# dac8.net
KiCad netlist of a schematic drawn in EAGLE
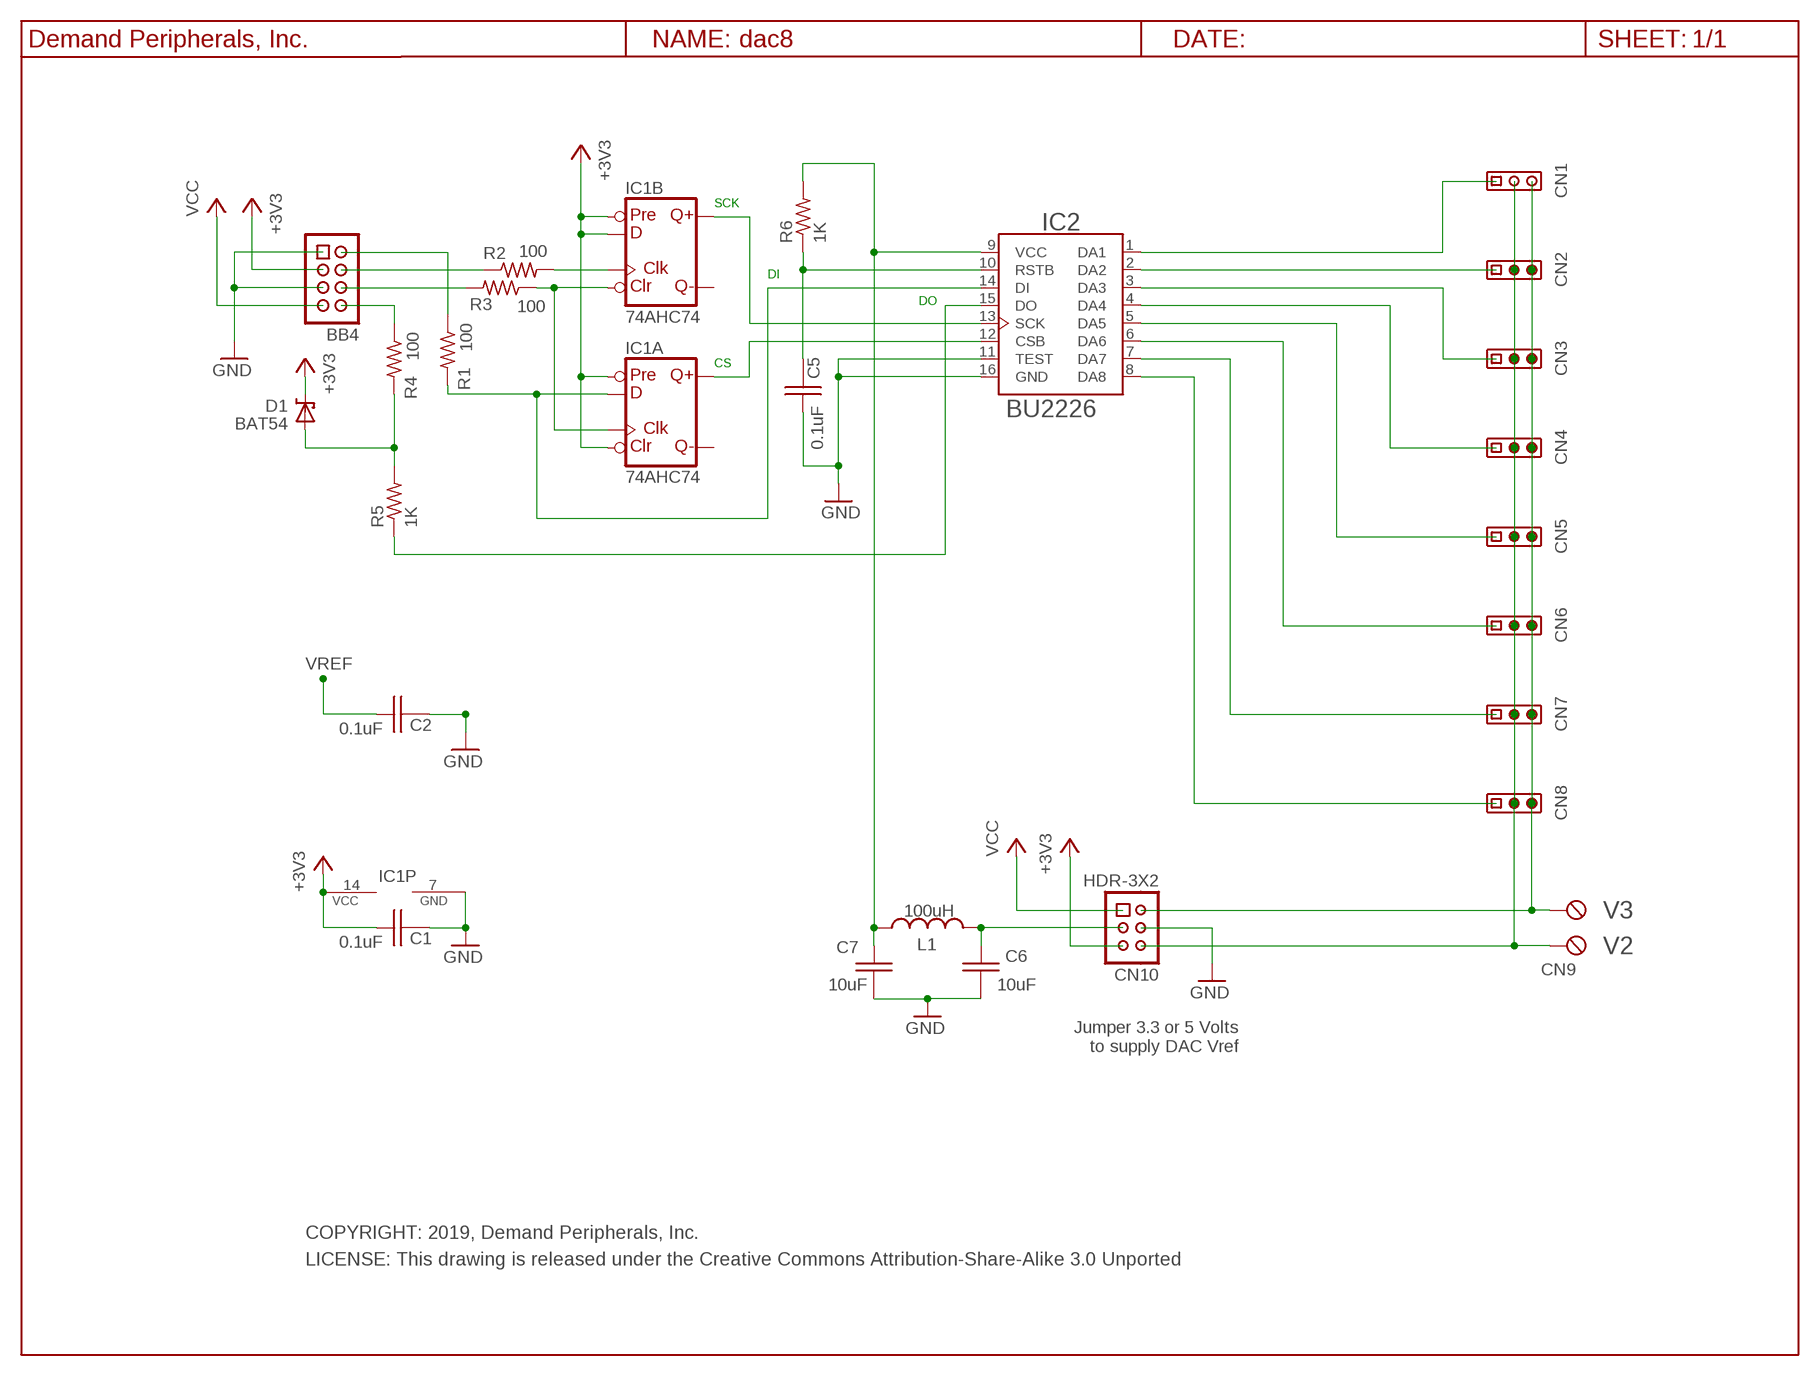
[diagram p0: schematic, sheet 1]

(export (version "E")
  (design (tool "Eeschema 10.0.6"))
  (components
    (comp (ref "BB4")
      (value "BB4")
      (footprint "eagle-import:HDR-4X2")
      (libsource (lib "eagle-import") (part "HDR-4X2-SHR"))
    )
    (comp (ref "C1")
      (value "0.1uF")
      (footprint "eagle-import:C0603")
      (libsource (lib "eagle-import") (part "C0.1UF_C0603"))
    )
    (comp (ref "C2")
      (value "0.1uF")
      (footprint "eagle-import:C0603")
      (libsource (lib "eagle-import") (part "C0.1UF_C0603"))
    )
    (comp (ref "C5")
      (value "0.1uF")
      (footprint "eagle-import:C0603")
      (libsource (lib "eagle-import") (part "C0.1UF_C0603"))
    )
    (comp (ref "C6")
      (value "10uF")
      (footprint "eagle-import:C0805")
      (libsource (lib "eagle-import") (part "C10UF35V_C0805"))
    )
    (comp (ref "C7")
      (value "10uF")
      (footprint "eagle-import:C0805")
      (libsource (lib "eagle-import") (part "C10UF35V_C0805"))
    )
    (comp (ref "CN1")
      (value "HDR-3X1")
      (footprint "eagle-import:HDR-3X1")
      (libsource (lib "eagle-import") (part "HDR-3X1"))
    )
    (comp (ref "CN2")
      (value "HDR-3X1")
      (footprint "eagle-import:HDR-3X1")
      (libsource (lib "eagle-import") (part "HDR-3X1"))
    )
    (comp (ref "CN3")
      (value "HDR-3X1")
      (footprint "eagle-import:HDR-3X1")
      (libsource (lib "eagle-import") (part "HDR-3X1"))
    )
    (comp (ref "CN4")
      (value "HDR-3X1")
      (footprint "eagle-import:HDR-3X1")
      (libsource (lib "eagle-import") (part "HDR-3X1"))
    )
    (comp (ref "CN5")
      (value "HDR-3X1")
      (footprint "eagle-import:HDR-3X1")
      (libsource (lib "eagle-import") (part "HDR-3X1"))
    )
    (comp (ref "CN6")
      (value "HDR-3X1")
      (footprint "eagle-import:HDR-3X1")
      (libsource (lib "eagle-import") (part "HDR-3X1"))
    )
    (comp (ref "CN7")
      (value "HDR-3X1")
      (footprint "eagle-import:HDR-3X1")
      (libsource (lib "eagle-import") (part "HDR-3X1"))
    )
    (comp (ref "CN8")
      (value "HDR-3X1")
      (footprint "eagle-import:HDR-3X1")
      (libsource (lib "eagle-import") (part "HDR-3X1"))
    )
    (comp (ref "CN9")
      (value "TBLK-5.08-X2")
      (footprint "eagle-import:TBLK-5.08-X2")
      (libsource (lib "eagle-import") (part "TBLK-5.08-X2"))
    )
    (comp (ref "CN10")
      (value "HDR-3X2")
      (footprint "eagle-import:HDR-3X2")
      (libsource (lib "eagle-import") (part "HDR-3X2"))
    )
    (comp (ref "D1")
      (value "BAT54")
      (footprint "eagle-import:SOT23")
      (libsource (lib "eagle-import") (part "BAT54"))
    )
    (comp (ref "IC1")
      (value "74AHC74")
      (footprint "eagle-import:SO14")
      (libsource (lib "eagle-import") (part "74AHC74SS"))
    )
    (comp (ref "IC2")
      (value "BU2226")
      (footprint "eagle-import:SO16")
      (libsource (lib "eagle-import") (part "BU2226"))
    )
    (comp (ref "L1")
      (value "100uH")
      (footprint "eagle-import:L0805")
      (libsource (lib "eagle-import") (part "L_100UH_0805"))
    )
    (comp (ref "R1")
      (value "100")
      (footprint "eagle-import:R0603")
      (libsource (lib "eagle-import") (part "R100_R0603"))
    )
    (comp (ref "R2")
      (value "100")
      (footprint "eagle-import:R0603")
      (libsource (lib "eagle-import") (part "R100_R0603"))
    )
    (comp (ref "R3")
      (value "100")
      (footprint "eagle-import:R0603")
      (libsource (lib "eagle-import") (part "R100_R0603"))
    )
    (comp (ref "R4")
      (value "100")
      (footprint "eagle-import:R0603")
      (libsource (lib "eagle-import") (part "R100_R0603"))
    )
    (comp (ref "R5")
      (value "1K")
      (footprint "eagle-import:R0603")
      (libsource (lib "eagle-import") (part "R1K_R0603"))
    )
    (comp (ref "R6")
      (value "1K")
      (footprint "eagle-import:R0603")
      (libsource (lib "eagle-import") (part "R1K_R0603"))
    )
    (comp (ref "S1")
      (value "DP_FRAME_L")
      (footprint "eagle-import:L_FRAME")
      (libsource (lib "eagle-import") (part "DP_FRAME_L"))
    )
  )
  (nets
    (net (code "1") (name "+3V3") (class "Default")
      (node (ref "BB4") (pin "3") (pinfunction "3_3") (pintype "passive"))
      (node (ref "C1") (pin "1") (pinfunction "1_1") (pintype "passive"))
      (node (ref "CN10") (pin "5") (pinfunction "5_5") (pintype "passive"))
      (node (ref "D1") (pin "3") (pinfunction "CC_3") (pintype "passive"))
      (node (ref "IC1") (pin "1") (pinfunction "CLR_1") (pintype "input"))
      (node (ref "IC1") (pin "10") (pinfunction "PRE_10") (pintype "input"))
      (node (ref "IC1") (pin "12") (pinfunction "D_12") (pintype "input"))
      (node (ref "IC1") (pin "14") (pinfunction "VCC_14") (pintype "power_in"))
      (node (ref "IC1") (pin "4") (pinfunction "PRE_4") (pintype "input"))
    )
    (net (code "2") (name "/VREF") (class "Default")
      (node (ref "C2") (pin "1") (pinfunction "1_1") (pintype "passive"))
      (node (ref "C7") (pin "1") (pinfunction "1_1") (pintype "passive"))
      (node (ref "IC2") (pin "9") (pinfunction "VCC_9") (pintype "power_in"))
      (node (ref "L1") (pin "1") (pinfunction "1_1") (pintype "passive"))
      (node (ref "R6") (pin "2") (pinfunction "2_2") (pintype "passive"))
    )
    (net (code "3") (name "GND") (class "Default")
      (node (ref "BB4") (pin "1") (pinfunction "1_1") (pintype "passive"))
      (node (ref "BB4") (pin "5") (pinfunction "5_5") (pintype "passive"))
      (node (ref "C1") (pin "2") (pinfunction "2_2") (pintype "passive"))
      (node (ref "C2") (pin "2") (pinfunction "2_2") (pintype "passive"))
      (node (ref "C5") (pin "1") (pinfunction "1_1") (pintype "passive"))
      (node (ref "C6") (pin "2") (pinfunction "2_2") (pintype "passive"))
      (node (ref "C7") (pin "2") (pinfunction "2_2") (pintype "passive"))
      (node (ref "CN10") (pin "4") (pinfunction "4_4") (pintype "passive"))
      (node (ref "IC1") (pin "7") (pinfunction "GND_7") (pintype "power_in"))
      (node (ref "IC2") (pin "11") (pinfunction "TEST_11") (pintype "input"))
      (node (ref "IC2") (pin "16") (pinfunction "GND_16") (pintype "power_in"))
    )
    (net (code "4") (name "Net-(BB4-Pad2)") (class "Default")
      (node (ref "BB4") (pin "2") (pinfunction "2_2") (pintype "passive"))
      (node (ref "R1") (pin "1") (pinfunction "1_1") (pintype "passive"))
    )
    (net (code "5") (name "Net-(BB4-Pad4)") (class "Default")
      (node (ref "BB4") (pin "4") (pinfunction "4_4") (pintype "passive"))
      (node (ref "R2") (pin "1") (pinfunction "1_1") (pintype "passive"))
    )
    (net (code "6") (name "Net-(BB4-Pad6)") (class "Default")
      (node (ref "BB4") (pin "6") (pinfunction "6_6") (pintype "passive"))
      (node (ref "R3") (pin "2") (pinfunction "2_2") (pintype "passive"))
    )
    (net (code "7") (name "Net-(BB4-Pad8)") (class "Default")
      (node (ref "BB4") (pin "8") (pinfunction "8_8") (pintype "passive"))
      (node (ref "R4") (pin "1") (pinfunction "1_1") (pintype "passive"))
    )
    (net (code "8") (name "Net-(C6-Pad1)") (class "Default")
      (node (ref "C6") (pin "1") (pinfunction "1_1") (pintype "passive"))
      (node (ref "CN10") (pin "3") (pinfunction "3_3") (pintype "passive"))
      (node (ref "L1") (pin "2") (pinfunction "2_2") (pintype "passive"))
    )
    (net (code "9") (name "Net-(CN9-KL)") (class "Default")
      (node (ref "CN1") (pin "2") (pinfunction "2_2") (pintype "passive"))
      (node (ref "CN10") (pin "6") (pinfunction "6_6") (pintype "passive"))
      (node (ref "CN2") (pin "2") (pinfunction "2_2") (pintype "passive"))
      (node (ref "CN3") (pin "2") (pinfunction "2_2") (pintype "passive"))
      (node (ref "CN4") (pin "2") (pinfunction "2_2") (pintype "passive"))
      (node (ref "CN5") (pin "2") (pinfunction "2_2") (pintype "passive"))
      (node (ref "CN6") (pin "2") (pinfunction "2_2") (pintype "passive"))
      (node (ref "CN7") (pin "2") (pinfunction "2_2") (pintype "passive"))
      (node (ref "CN8") (pin "2") (pinfunction "2_2") (pintype "passive"))
      (node (ref "CN9") (pin "1") (pinfunction "KL_1") (pintype "passive"))
    )
    (net (code "10") (name "Net-(CN9-KL1)") (class "Default")
      (node (ref "CN1") (pin "3") (pinfunction "3_3") (pintype "passive"))
      (node (ref "CN10") (pin "2") (pinfunction "2_2") (pintype "passive"))
      (node (ref "CN2") (pin "3") (pinfunction "3_3") (pintype "passive"))
      (node (ref "CN3") (pin "3") (pinfunction "3_3") (pintype "passive"))
      (node (ref "CN4") (pin "3") (pinfunction "3_3") (pintype "passive"))
      (node (ref "CN5") (pin "3") (pinfunction "3_3") (pintype "passive"))
      (node (ref "CN6") (pin "3") (pinfunction "3_3") (pintype "passive"))
      (node (ref "CN7") (pin "3") (pinfunction "3_3") (pintype "passive"))
      (node (ref "CN8") (pin "3") (pinfunction "3_3") (pintype "passive"))
      (node (ref "CN9") (pin "2") (pinfunction "KL1_2") (pintype "passive"))
    )
    (net (code "11") (name "Net-(D1-A)") (class "Default")
      (node (ref "D1") (pin "1") (pinfunction "A_1") (pintype "passive"))
      (node (ref "R4") (pin "2") (pinfunction "2_2") (pintype "passive"))
      (node (ref "R5") (pin "2") (pinfunction "2_2") (pintype "passive"))
    )
    (net (code "12") (name "Net-(IC1A-CLK)") (class "Default")
      (node (ref "IC1") (pin "13") (pinfunction "CLR_13") (pintype "input"))
      (node (ref "IC1") (pin "3") (pinfunction "CLK_3") (pintype "input"))
      (node (ref "R3") (pin "1") (pinfunction "1_1") (pintype "passive"))
    )
    (net (code "13") (name "Net-(IC1A-D)") (class "Default")
      (node (ref "IC1") (pin "2") (pinfunction "D_2") (pintype "input"))
      (node (ref "IC2") (pin "14") (pinfunction "DI_14") (pintype "input"))
      (node (ref "R1") (pin "2") (pinfunction "2_2") (pintype "passive"))
    )
    (net (code "14") (name "Net-(IC1A-Q)") (class "Default")
      (node (ref "IC1") (pin "5") (pinfunction "Q_5") (pintype "output"))
      (node (ref "IC2") (pin "12") (pinfunction "CSB_12") (pintype "input"))
    )
    (net (code "15") (name "Net-(IC1B-CLK)") (class "Default")
      (node (ref "IC1") (pin "11") (pinfunction "CLK_11") (pintype "input"))
      (node (ref "R2") (pin "2") (pinfunction "2_2") (pintype "passive"))
    )
    (net (code "16") (name "Net-(IC1B-Q)") (class "Default")
      (node (ref "IC1") (pin "9") (pinfunction "Q_9") (pintype "output"))
      (node (ref "IC2") (pin "13") (pinfunction "SCK_13") (pintype "input"))
    )
    (net (code "17") (name "Net-(IC2-DA1)") (class "Default")
      (node (ref "CN1") (pin "1") (pinfunction "1_1") (pintype "passive"))
      (node (ref "IC2") (pin "1") (pinfunction "DA1_1") (pintype "output"))
    )
    (net (code "18") (name "Net-(IC2-DA2)") (class "Default")
      (node (ref "CN2") (pin "1") (pinfunction "1_1") (pintype "passive"))
      (node (ref "IC2") (pin "2") (pinfunction "DA2_2") (pintype "output"))
    )
    (net (code "19") (name "Net-(IC2-DA3)") (class "Default")
      (node (ref "CN3") (pin "1") (pinfunction "1_1") (pintype "passive"))
      (node (ref "IC2") (pin "3") (pinfunction "DA3_3") (pintype "output"))
    )
    (net (code "20") (name "Net-(IC2-DA4)") (class "Default")
      (node (ref "CN4") (pin "1") (pinfunction "1_1") (pintype "passive"))
      (node (ref "IC2") (pin "4") (pinfunction "DA4_4") (pintype "output"))
    )
    (net (code "21") (name "Net-(IC2-DA5)") (class "Default")
      (node (ref "CN5") (pin "1") (pinfunction "1_1") (pintype "passive"))
      (node (ref "IC2") (pin "5") (pinfunction "DA5_5") (pintype "output"))
    )
    (net (code "22") (name "Net-(IC2-DA6)") (class "Default")
      (node (ref "CN6") (pin "1") (pinfunction "1_1") (pintype "passive"))
      (node (ref "IC2") (pin "6") (pinfunction "DA6_6") (pintype "output"))
    )
    (net (code "23") (name "Net-(IC2-DA7)") (class "Default")
      (node (ref "CN7") (pin "1") (pinfunction "1_1") (pintype "passive"))
      (node (ref "IC2") (pin "7") (pinfunction "DA7_7") (pintype "output"))
    )
    (net (code "24") (name "Net-(IC2-DA8)") (class "Default")
      (node (ref "CN8") (pin "1") (pinfunction "1_1") (pintype "passive"))
      (node (ref "IC2") (pin "8") (pinfunction "DA8_8") (pintype "output"))
    )
    (net (code "25") (name "Net-(IC2-DO)") (class "Default")
      (node (ref "IC2") (pin "15") (pinfunction "DO_15") (pintype "output"))
      (node (ref "R5") (pin "1") (pinfunction "1_1") (pintype "passive"))
    )
    (net (code "26") (name "Net-(IC2-RSTB)") (class "Default")
      (node (ref "C5") (pin "2") (pinfunction "2_2") (pintype "passive"))
      (node (ref "IC2") (pin "10") (pinfunction "RSTB_10") (pintype "input"))
      (node (ref "R6") (pin "1") (pinfunction "1_1") (pintype "passive"))
    )
    (net (code "27") (name "VCC") (class "Default")
      (node (ref "BB4") (pin "7") (pinfunction "7_7") (pintype "passive"))
      (node (ref "CN10") (pin "1") (pinfunction "1_1") (pintype "passive"))
    )
    (net (code "28") (name "unconnected-(IC1A-~{Q}-Pad6)") (class "Default")
      (node (ref "IC1") (pin "6") (pinfunction "~{Q}_6") (pintype "output"))
    )
    (net (code "29") (name "unconnected-(IC1B-~{Q}-Pad8)") (class "Default")
      (node (ref "IC1") (pin "8") (pinfunction "~{Q}_8") (pintype "output"))
    )
  )
)
